# Sheet_1_2025-02-26.net
KiCad netlist of a schematic drawn in Altium Designer
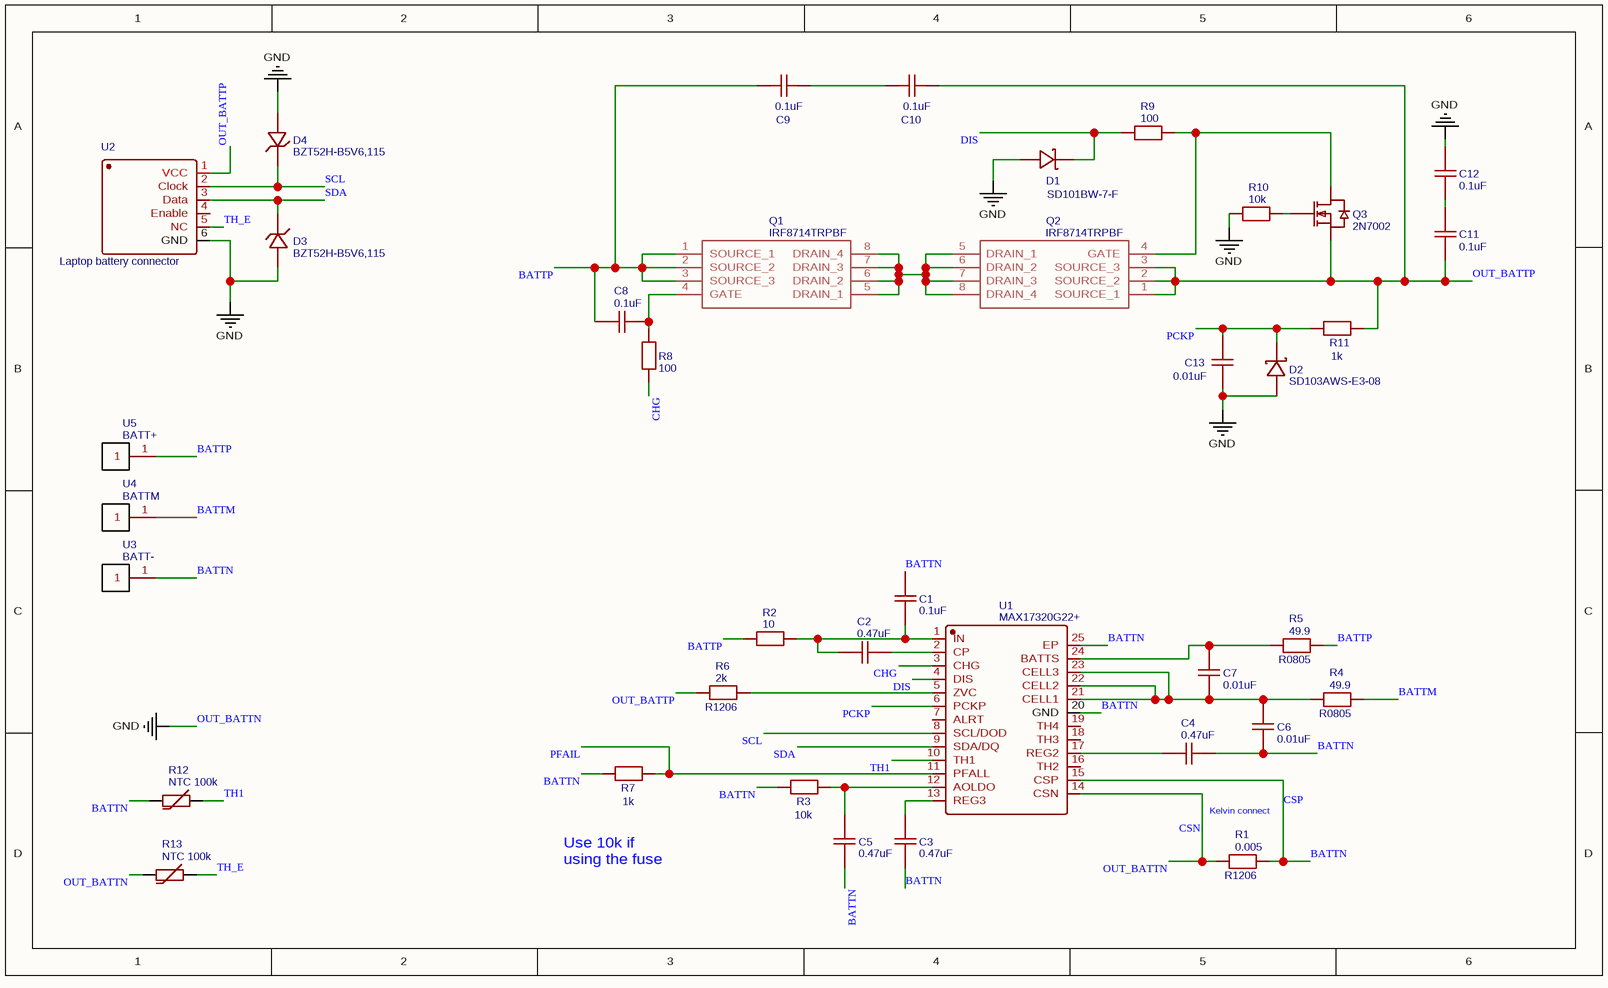
[diagram p0: Sheet_1_2025-02-26.schdoc]

(export (version "E")
  (design (tool "Eeschema 10.0.6"))
  (components
    (comp (ref "C1")
      (value "0.1uF")
      (fields (field (name "CONTRIBUTOR") "LCEDA_Lib"))
      (libsource (lib "altium-import") (part "root_1_0.1uF_"))
    )
    (comp (ref "C2")
      (value "0.47uF")
      (fields (field (name "CONTRIBUTOR") "LCEDA_Lib"))
      (libsource (lib "altium-import") (part "root_2_0.47uF_"))
    )
    (comp (ref "C3")
      (value "0.47uF")
      (fields (field (name "CONTRIBUTOR") "LCEDA_Lib"))
      (libsource (lib "altium-import") (part "root_1_0.47uF_"))
    )
    (comp (ref "C4")
      (value "0.47uF")
      (fields (field (name "CONTRIBUTOR") "LCEDA_Lib"))
      (libsource (lib "altium-import") (part "root_2_0.47uF_"))
    )
    (comp (ref "C5")
      (value "0.47uF")
      (fields (field (name "CONTRIBUTOR") "LCEDA_Lib"))
      (libsource (lib "altium-import") (part "root_3_0.47uF_"))
    )
    (comp (ref "C6")
      (value "0.01uF")
      (fields (field (name "CONTRIBUTOR") "LCEDA_Lib"))
      (libsource (lib "altium-import") (part "root_1_0.01uF_"))
    )
    (comp (ref "C7")
      (value "0.01uF")
      (fields (field (name "CONTRIBUTOR") "LCEDA_Lib"))
      (libsource (lib "altium-import") (part "root_3_0.01uF_"))
    )
    (comp (ref "C8")
      (value "0.1uF")
      (fields (field (name "CONTRIBUTOR") "LCEDA_Lib"))
      (libsource (lib "altium-import") (part "root_2_0.1uF_"))
    )
    (comp (ref "C9")
      (value "0.1uF")
      (fields (field (name "CONTRIBUTOR") "LCEDA_Lib"))
      (libsource (lib "altium-import") (part "root_2_0.1uF_"))
    )
    (comp (ref "C10")
      (value "0.1uF")
      (fields (field (name "CONTRIBUTOR") "LCEDA_Lib"))
      (libsource (lib "altium-import") (part "root_2_0.1uF_"))
    )
    (comp (ref "C11")
      (value "0.1uF")
      (fields (field (name "CONTRIBUTOR") "LCEDA_Lib"))
      (libsource (lib "altium-import") (part "root_1_0.1uF_"))
    )
    (comp (ref "C12")
      (value "0.1uF")
      (fields (field (name "CONTRIBUTOR") "LCEDA_Lib"))
      (libsource (lib "altium-import") (part "root_1_0.1uF_"))
    )
    (comp (ref "C13")
      (value "0.01uF")
      (fields (field (name "CONTRIBUTOR") "LCEDA_Lib"))
      (libsource (lib "altium-import") (part "root_3_0.01uF_"))
    )
    (comp (ref "D1")
      (value "SD101BW-7-F")
      (fields
        (field (name "MANUFACTURER") "Diodes Incorporated")
        (field (name "MANUFACTURER PART") "SD101BWS-7-F")
        (field (name "CONTRIBUTOR") "LCSC")
      )
      (libsource (lib "altium-import") (part "root_2_SD101BW-7-F_"))
    )
    (comp (ref "D2")
      (value "SD103AWS-E3-08")
      (fields (field (name "MANUFACTURER") "VISHAY") (field (name "CONTRIBUTOR") "LCSC"))
      (libsource (lib "altium-import") (part "root_3_SD103AWS-E3-08_"))
    )
    (comp (ref "D3")
      (value "BZT52H-B5V6,115")
      (fields (field (name "MANUFACTURER") "Nexperia") (field (name "CONTRIBUTOR") "LCSC"))
      (libsource (lib "altium-import") (part "root_3_BZT52H-B5V6,115_"))
    )
    (comp (ref "D4")
      (value "BZT52H-B5V6,115")
      (fields (field (name "MANUFACTURER") "Nexperia") (field (name "CONTRIBUTOR") "LCSC"))
      (libsource (lib "altium-import") (part "root_1_BZT52H-B5V6,115_"))
    )
    (comp (ref "Q1")
      (value "IRF8714TRPBF")
      (fields (field (name "CONTRIBUTOR") "Jorge Ignacio Sánchez Flores"))
      (libsource (lib "altium-import") (part "root_0_IRF8714TRPBF_"))
    )
    (comp (ref "Q2")
      (value "IRF8714TRPBF")
      (fields (field (name "CONTRIBUTOR") "Jorge Ignacio Sánchez Flores"))
      (libsource (lib "altium-import") (part "root_2_IRF8714TRPBF_"))
    )
    (comp (ref "Q3")
      (value "2N7002")
      (fields (field (name "MANUFACTURER") "CJ"))
      (libsource (lib "altium-import") (part "root_0_2N7002_"))
    )
    (comp (ref "R1")
      (value "0.005")
      (fields (field (name "CONTRIBUTOR") "LCEDA_Lib"))
      (libsource (lib "altium-import") (part "root_0_0.005_"))
    )
    (comp (ref "R2")
      (value "10")
      (fields (field (name "CONTRIBUTOR") "LCEDA_Lib"))
      (libsource (lib "altium-import") (part "root_0_10_"))
    )
    (comp (ref "R3")
      (value "10k")
      (fields (field (name "CONTRIBUTOR") "LCEDA_Lib"))
      (libsource (lib "altium-import") (part "root_0_10k_"))
    )
    (comp (ref "R4")
      (value "49.9")
      (fields (field (name "CONTRIBUTOR") "LCEDA_Lib"))
      (libsource (lib "altium-import") (part "root_0_49.9_"))
    )
    (comp (ref "R5")
      (value "49.9")
      (fields
        (field (name "MANUFACTURER PART") "RMC080549.91%N")
        (field (name "MANUFACTURER") "Tyohm")
        (field (name "CONTRIBUTOR") "LCEDA_Lib")
      )
      (libsource (lib "altium-import") (part "root_0_49.9_"))
    )
    (comp (ref "R6")
      (value "2k")
      (fields (field (name "CONTRIBUTOR") "LCEDA_Lib"))
      (libsource (lib "altium-import") (part "root_0_2k_"))
    )
    (comp (ref "R7")
      (value "1k")
      (fields (field (name "CONTRIBUTOR") "LCEDA_Lib"))
      (libsource (lib "altium-import") (part "root_0_1k_"))
    )
    (comp (ref "R8")
      (value "100")
      (fields (field (name "CONTRIBUTOR") "LCEDA_Lib"))
      (libsource (lib "altium-import") (part "root_1_100_"))
    )
    (comp (ref "R9")
      (value "100")
      (fields (field (name "CONTRIBUTOR") "LCEDA_Lib"))
      (libsource (lib "altium-import") (part "root_0_100_"))
    )
    (comp (ref "R10")
      (value "10k")
      (fields (field (name "CONTRIBUTOR") "LCEDA_Lib"))
      (libsource (lib "altium-import") (part "root_0_10k_"))
    )
    (comp (ref "R11")
      (value "1k")
      (fields (field (name "CONTRIBUTOR") "LCEDA_Lib"))
      (libsource (lib "altium-import") (part "root_0_1k_"))
    )
    (comp (ref "R12")
      (value "NTC 100k")
      (fields (field (name "MANUFACTURER") "FH") (field (name "MANUFACTURER PART") "CMFB102J3200HANT"))
      (libsource (lib "altium-import") (part "root_0_NTC 100k_"))
    )
    (comp (ref "R13")
      (value "NTC 100k")
      (fields (field (name "MANUFACTURER") "FH") (field (name "MANUFACTURER PART") "CMFB102J3200HANT"))
      (libsource (lib "altium-import") (part "root_0_NTC 100k_"))
    )
    (comp (ref "U1")
      (value "MAX17320G22+")
      (fields (field (name "CONTRIBUTOR") "LCSC"))
      (libsource (lib "altium-import") (part "root_0_MAX17320G22+_"))
    )
    (comp (ref "U2")
      (value "Laptop battery connector")
      (fields (field (name "CONTRIBUTOR") "PixelCircuit"))
      (libsource (lib "altium-import") (part "root_0_Laptop battery connector_"))
    )
    (comp (ref "U3")
      (value "BATT-")
      (fields (field (name "CONTRIBUTOR") "luisf18"))
      (libsource (lib "altium-import") (part "root_2_BATT-_"))
    )
    (comp (ref "U4")
      (value "BATTM")
      (fields (field (name "CONTRIBUTOR") "luisf18"))
      (libsource (lib "altium-import") (part "root_2_BATTM_"))
    )
    (comp (ref "U5")
      (value "BATT+")
      (fields (field (name "CONTRIBUTOR") "luisf18"))
      (libsource (lib "altium-import") (part "root_2_BATT+_"))
    )
  )
  (nets
    (net (code "1") (name "/BATTM") (class "Default")
      (node (ref "R4") (pin "2") (pinfunction "2_2") (pintype "passive"))
      (node (ref "U4") (pin "1") (pinfunction "1_1") (pintype "passive"))
    )
    (net (code "2") (name "/BATTN") (class "Default")
      (node (ref "C1") (pin "2") (pinfunction "2_2") (pintype "passive"))
      (node (ref "C3") (pin "1") (pinfunction "1_1") (pintype "passive"))
      (node (ref "C4") (pin "1") (pinfunction "1_1") (pintype "passive"))
      (node (ref "C5") (pin "2") (pinfunction "2_2") (pintype "passive"))
      (node (ref "C6") (pin "1") (pinfunction "1_1") (pintype "passive"))
      (node (ref "R1") (pin "2") (pinfunction "2_2") (pintype "passive"))
      (node (ref "R12") (pin "1") (pinfunction "1_1") (pintype "passive"))
      (node (ref "R3") (pin "1") (pinfunction "1_1") (pintype "passive"))
      (node (ref "R7") (pin "1") (pinfunction "1_1") (pintype "passive"))
      (node (ref "U1") (pin "15") (pinfunction "CSP_15") (pintype "passive"))
      (node (ref "U1") (pin "20") (pinfunction "GND_20") (pintype "passive"))
      (node (ref "U1") (pin "25") (pinfunction "EP_25") (pintype "passive"))
      (node (ref "U3") (pin "1") (pinfunction "1_1") (pintype "passive"))
    )
    (net (code "3") (name "/BATTP") (class "Default")
      (node (ref "C8") (pin "2") (pinfunction "2_2") (pintype "passive"))
      (node (ref "C9") (pin "2") (pinfunction "2_2") (pintype "passive"))
      (node (ref "Q1") (pin "1") (pinfunction "SOURCE_1_1") (pintype "passive"))
      (node (ref "Q1") (pin "2") (pinfunction "SOURCE_2_2") (pintype "passive"))
      (node (ref "Q1") (pin "3") (pinfunction "SOURCE_3_3") (pintype "passive"))
      (node (ref "R2") (pin "1") (pinfunction "1_1") (pintype "passive"))
      (node (ref "R5") (pin "2") (pinfunction "2_2") (pintype "passive"))
      (node (ref "U5") (pin "1") (pinfunction "1_1") (pintype "passive"))
    )
    (net (code "4") (name "/CHG") (class "Default")
      (node (ref "R8") (pin "1") (pinfunction "1_1") (pintype "passive"))
      (node (ref "U1") (pin "3") (pinfunction "CHG_3") (pintype "passive"))
    )
    (net (code "5") (name "/DIS") (class "Default")
      (node (ref "D1") (pin "1") (pinfunction "C_1") (pintype "passive"))
      (node (ref "R9") (pin "1") (pinfunction "1_1") (pintype "passive"))
      (node (ref "U1") (pin "4") (pinfunction "DIS_4") (pintype "passive"))
    )
    (net (code "6") (name "/OUT_BATTP") (class "Default")
      (node (ref "C10") (pin "1") (pinfunction "1_1") (pintype "passive"))
      (node (ref "C11") (pin "1") (pinfunction "1_1") (pintype "passive"))
      (node (ref "Q2") (pin "1") (pinfunction "SOURCE_1_1") (pintype "passive"))
      (node (ref "Q2") (pin "2") (pinfunction "SOURCE_2_2") (pintype "passive"))
      (node (ref "Q2") (pin "3") (pinfunction "SOURCE_3_3") (pintype "passive"))
      (node (ref "Q3") (pin "2") (pinfunction "S_2") (pintype "passive"))
      (node (ref "R11") (pin "2") (pinfunction "2_2") (pintype "passive"))
      (node (ref "R6") (pin "1") (pinfunction "1_1") (pintype "passive"))
      (node (ref "U2") (pin "1") (pinfunction "VCC_1") (pintype "passive"))
    )
    (net (code "7") (name "/PCKP") (class "Default")
      (node (ref "C13") (pin "1") (pinfunction "1_1") (pintype "passive"))
      (node (ref "D2") (pin "1") (pinfunction "K_1") (pintype "passive"))
      (node (ref "R11") (pin "1") (pinfunction "1_1") (pintype "passive"))
      (node (ref "U1") (pin "6") (pinfunction "PCKP_6") (pintype "passive"))
    )
    (net (code "8") (name "/PFAIL") (class "Default")
      (node (ref "R7") (pin "2") (pinfunction "2_2") (pintype "passive"))
      (node (ref "U1") (pin "11") (pinfunction "PFALL_11") (pintype "passive"))
    )
    (net (code "9") (name "/SCL") (class "Default")
      (node (ref "D4") (pin "1") (pinfunction "C_1") (pintype "passive"))
      (node (ref "U1") (pin "8") (pinfunction "SCL/DOD_8") (pintype "passive"))
      (node (ref "U2") (pin "2") (pinfunction "Clock_2") (pintype "passive"))
    )
    (net (code "10") (name "/SDA") (class "Default")
      (node (ref "D3") (pin "1") (pinfunction "C_1") (pintype "passive"))
      (node (ref "U1") (pin "9") (pinfunction "SDA/DQ_9") (pintype "passive"))
      (node (ref "U2") (pin "3") (pinfunction "Data_3") (pintype "passive"))
    )
    (net (code "11") (name "/TH1") (class "Default")
      (node (ref "R12") (pin "2") (pinfunction "2_2") (pintype "passive"))
      (node (ref "U1") (pin "10") (pinfunction "TH1_10") (pintype "passive"))
    )
    (net (code "12") (name "/TH_E") (class "Default")
      (node (ref "R13") (pin "2") (pinfunction "2_2") (pintype "passive"))
      (node (ref "U2") (pin "5") (pinfunction "NC_5") (pintype "passive"))
    )
    (net (code "13") (name "GND") (class "Default")
      (node (ref "C12") (pin "2") (pinfunction "2_2") (pintype "passive"))
      (node (ref "C13") (pin "2") (pinfunction "2_2") (pintype "passive"))
      (node (ref "D1") (pin "2") (pinfunction "A_2") (pintype "passive"))
      (node (ref "D2") (pin "2") (pinfunction "A_2") (pintype "passive"))
      (node (ref "D3") (pin "2") (pinfunction "A_2") (pintype "passive"))
      (node (ref "D4") (pin "2") (pinfunction "A_2") (pintype "passive"))
      (node (ref "R1") (pin "1") (pinfunction "1_1") (pintype "passive"))
      (node (ref "R10") (pin "1") (pinfunction "1_1") (pintype "passive"))
      (node (ref "R13") (pin "1") (pinfunction "1_1") (pintype "passive"))
      (node (ref "U1") (pin "14") (pinfunction "CSN_14") (pintype "passive"))
      (node (ref "U2") (pin "6") (pinfunction "GND_6") (pintype "passive"))
    )
    (net (code "14") (name "Net-(C10-Pad2)") (class "Default")
      (node (ref "C10") (pin "2") (pinfunction "2_2") (pintype "passive"))
      (node (ref "C9") (pin "1") (pinfunction "1_1") (pintype "passive"))
    )
    (net (code "15") (name "Net-(C11-Pad2)") (class "Default")
      (node (ref "C11") (pin "2") (pinfunction "2_2") (pintype "passive"))
      (node (ref "C12") (pin "1") (pinfunction "1_1") (pintype "passive"))
    )
    (net (code "16") (name "Net-(Q1-DRAIN_1)") (class "Default")
      (node (ref "Q1") (pin "5") (pinfunction "DRAIN_1_5") (pintype "passive"))
      (node (ref "Q1") (pin "6") (pinfunction "DRAIN_2_6") (pintype "passive"))
      (node (ref "Q1") (pin "7") (pinfunction "DRAIN_3_7") (pintype "passive"))
      (node (ref "Q1") (pin "8") (pinfunction "DRAIN_4_8") (pintype "passive"))
      (node (ref "Q2") (pin "5") (pinfunction "DRAIN_1_5") (pintype "passive"))
      (node (ref "Q2") (pin "6") (pinfunction "DRAIN_2_6") (pintype "passive"))
      (node (ref "Q2") (pin "7") (pinfunction "DRAIN_3_7") (pintype "passive"))
      (node (ref "Q2") (pin "8") (pinfunction "DRAIN_4_8") (pintype "passive"))
    )
    (net (code "17") (name "Net-(Q1-GATE)") (class "Default")
      (node (ref "C8") (pin "1") (pinfunction "1_1") (pintype "passive"))
      (node (ref "Q1") (pin "4") (pinfunction "GATE_4") (pintype "passive"))
      (node (ref "R8") (pin "2") (pinfunction "2_2") (pintype "passive"))
    )
    (net (code "18") (name "Net-(Q2-GATE)") (class "Default")
      (node (ref "Q2") (pin "4") (pinfunction "GATE_4") (pintype "passive"))
      (node (ref "Q3") (pin "3") (pinfunction "D_3") (pintype "passive"))
      (node (ref "R9") (pin "2") (pinfunction "2_2") (pintype "passive"))
    )
    (net (code "19") (name "Net-(Q3-G)") (class "Default")
      (node (ref "Q3") (pin "1") (pinfunction "G_1") (pintype "passive"))
      (node (ref "R10") (pin "2") (pinfunction "2_2") (pintype "passive"))
    )
    (net (code "20") (name "Net-(U1-AOLDO)") (class "Default")
      (node (ref "C5") (pin "1") (pinfunction "1_1") (pintype "passive"))
      (node (ref "R3") (pin "2") (pinfunction "2_2") (pintype "passive"))
      (node (ref "U1") (pin "12") (pinfunction "AOLDO_12") (pintype "passive"))
    )
    (net (code "21") (name "Net-(U1-BATTS)") (class "Default")
      (node (ref "C7") (pin "1") (pinfunction "1_1") (pintype "passive"))
      (node (ref "R5") (pin "1") (pinfunction "1_1") (pintype "passive"))
      (node (ref "U1") (pin "24") (pinfunction "BATTS_24") (pintype "passive"))
    )
    (net (code "22") (name "Net-(U1-CELL1)") (class "Default")
      (node (ref "C6") (pin "2") (pinfunction "2_2") (pintype "passive"))
      (node (ref "C7") (pin "2") (pinfunction "2_2") (pintype "passive"))
      (node (ref "R4") (pin "1") (pinfunction "1_1") (pintype "passive"))
      (node (ref "U1") (pin "21") (pinfunction "CELL1_21") (pintype "passive"))
      (node (ref "U1") (pin "22") (pinfunction "CELL2_22") (pintype "passive"))
      (node (ref "U1") (pin "23") (pinfunction "CELL3_23") (pintype "passive"))
    )
    (net (code "23") (name "Net-(U1-CP)") (class "Default")
      (node (ref "C2") (pin "1") (pinfunction "1_1") (pintype "passive"))
      (node (ref "U1") (pin "2") (pinfunction "CP_2") (pintype "passive"))
    )
    (net (code "24") (name "Net-(U1-IN)") (class "Default")
      (node (ref "C1") (pin "1") (pinfunction "1_1") (pintype "passive"))
      (node (ref "C2") (pin "2") (pinfunction "2_2") (pintype "passive"))
      (node (ref "R2") (pin "2") (pinfunction "2_2") (pintype "passive"))
      (node (ref "U1") (pin "1") (pinfunction "IN_1") (pintype "passive"))
    )
    (net (code "25") (name "Net-(U1-REG2)") (class "Default")
      (node (ref "C4") (pin "2") (pinfunction "2_2") (pintype "passive"))
      (node (ref "U1") (pin "17") (pinfunction "REG2_17") (pintype "passive"))
    )
    (net (code "26") (name "Net-(U1-REG3)") (class "Default")
      (node (ref "C3") (pin "2") (pinfunction "2_2") (pintype "passive"))
      (node (ref "U1") (pin "13") (pinfunction "REG3_13") (pintype "passive"))
    )
    (net (code "27") (name "Net-(U1-ZVC)") (class "Default")
      (node (ref "R6") (pin "2") (pinfunction "2_2") (pintype "passive"))
      (node (ref "U1") (pin "5") (pinfunction "ZVC_5") (pintype "passive"))
    )
    (net (code "28") (name "unconnected-(U1-ALRT-Pad7)") (class "Default")
      (node (ref "U1") (pin "7") (pinfunction "ALRT_7") (pintype "passive"))
    )
    (net (code "29") (name "unconnected-(U1-TH2-Pad16)") (class "Default")
      (node (ref "U1") (pin "16") (pinfunction "TH2_16") (pintype "passive"))
    )
    (net (code "30") (name "unconnected-(U1-TH3-Pad18)") (class "Default")
      (node (ref "U1") (pin "18") (pinfunction "TH3_18") (pintype "passive"))
    )
    (net (code "31") (name "unconnected-(U1-TH4-Pad19)") (class "Default")
      (node (ref "U1") (pin "19") (pinfunction "TH4_19") (pintype "passive"))
    )
    (net (code "32") (name "unconnected-(U2-Enable-Pad4)") (class "Default")
      (node (ref "U2") (pin "4") (pinfunction "Enable_4") (pintype "passive"))
    )
  )
)
